# 12V-Rail_IGVC_14-15.net
KiCad netlist of a schematic drawn in EAGLE
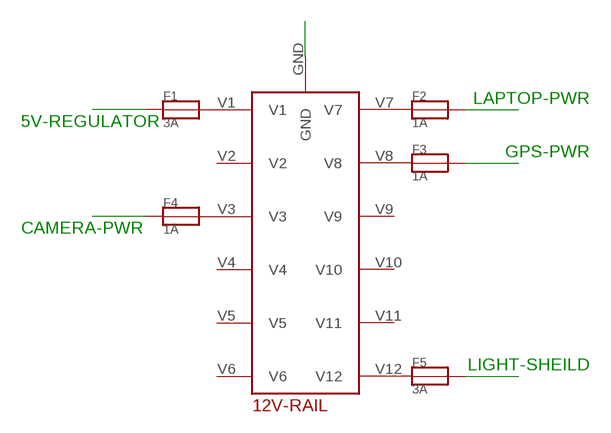
[diagram p0: schematic, sheet 1]

(export (version "E")
  (design (tool "Eeschema 10.0.6"))
  (components
    (comp (ref "12V-RAIL")
      (value "FUSEBLOCK-12")
      (footprint "eagle-import:FUSEBLOCK-12PT")
      (libsource (lib "eagle-import") (part "FUSEBLOCK-12"))
    )
    (comp (ref "F1")
      (value "3A")
      (footprint "eagle-import:FUSE")
      (libsource (lib "eagle-import") (part "FUSE"))
    )
    (comp (ref "F2")
      (value "1A")
      (footprint "eagle-import:FUSE")
      (libsource (lib "eagle-import") (part "FUSE"))
    )
    (comp (ref "F3")
      (value "1A")
      (footprint "eagle-import:FUSE")
      (libsource (lib "eagle-import") (part "FUSE"))
    )
    (comp (ref "F4")
      (value "1A")
      (footprint "eagle-import:FUSE")
      (libsource (lib "eagle-import") (part "FUSE"))
    )
    (comp (ref "F5")
      (value "3A")
      (footprint "eagle-import:FUSE")
      (libsource (lib "eagle-import") (part "FUSE"))
    )
  )
  (nets
    (net (code "1") (name "/V2") (class "Default")
      (node (ref "12V-RAIL") (pin "V2") (pinfunction "V2_V2") (pintype "power_in"))
    )
    (net (code "2") (name "/V4") (class "Default")
      (node (ref "12V-RAIL") (pin "V4") (pinfunction "V4_V4") (pintype "power_in"))
    )
    (net (code "3") (name "/V5") (class "Default")
      (node (ref "12V-RAIL") (pin "V5") (pinfunction "V5_V5") (pintype "power_in"))
    )
    (net (code "4") (name "/V6") (class "Default")
      (node (ref "12V-RAIL") (pin "V6") (pinfunction "V6_V6") (pintype "power_in"))
    )
    (net (code "5") (name "/V9") (class "Default")
      (node (ref "12V-RAIL") (pin "V9") (pinfunction "V9_V9") (pintype "power_in"))
    )
    (net (code "6") (name "/V10") (class "Default")
      (node (ref "12V-RAIL") (pin "V10") (pinfunction "V10_V10") (pintype "power_in"))
    )
    (net (code "7") (name "/V11") (class "Default")
      (node (ref "12V-RAIL") (pin "V11") (pinfunction "V11_V11") (pintype "power_in"))
    )
    (net (code "8") (name "Net-(12V-RAIL-PadV1)") (class "Default")
      (node (ref "12V-RAIL") (pin "V1") (pinfunction "V1_V1") (pintype "power_in"))
      (node (ref "F1") (pin "P$2") (pinfunction "P$2_P$2") (pintype "bidirectional"))
    )
    (net (code "9") (name "Net-(12V-RAIL-PadV3)") (class "Default")
      (node (ref "12V-RAIL") (pin "V3") (pinfunction "V3_V3") (pintype "power_in"))
      (node (ref "F4") (pin "P$2") (pinfunction "P$2_P$2") (pintype "bidirectional"))
    )
    (net (code "10") (name "Net-(12V-RAIL-PadV7)") (class "Default")
      (node (ref "12V-RAIL") (pin "V7") (pinfunction "V7_V7") (pintype "power_in"))
      (node (ref "F2") (pin "P$1") (pinfunction "P$1_P$1") (pintype "bidirectional"))
    )
    (net (code "11") (name "Net-(12V-RAIL-PadV8)") (class "Default")
      (node (ref "12V-RAIL") (pin "V8") (pinfunction "V8_V8") (pintype "power_in"))
      (node (ref "F3") (pin "P$1") (pinfunction "P$1_P$1") (pintype "bidirectional"))
    )
    (net (code "12") (name "Net-(12V-RAIL-PadV12)") (class "Default")
      (node (ref "12V-RAIL") (pin "V12") (pinfunction "V12_V12") (pintype "power_in"))
      (node (ref "F5") (pin "P$1") (pinfunction "P$1_P$1") (pintype "bidirectional"))
    )
    (net (code "13") (name "unconnected-(12V-RAIL-PadGND)") (class "Default")
      (node (ref "12V-RAIL") (pin "GND") (pinfunction "GND_GND") (pintype "power_in"))
    )
    (net (code "14") (name "unconnected-(F1-PadP$1)") (class "Default")
      (node (ref "F1") (pin "P$1") (pinfunction "P$1_P$1") (pintype "bidirectional"))
    )
    (net (code "15") (name "unconnected-(F2-PadP$2)") (class "Default")
      (node (ref "F2") (pin "P$2") (pinfunction "P$2_P$2") (pintype "bidirectional"))
    )
    (net (code "16") (name "unconnected-(F3-PadP$2)") (class "Default")
      (node (ref "F3") (pin "P$2") (pinfunction "P$2_P$2") (pintype "bidirectional"))
    )
    (net (code "17") (name "unconnected-(F4-PadP$1)") (class "Default")
      (node (ref "F4") (pin "P$1") (pinfunction "P$1_P$1") (pintype "bidirectional"))
    )
    (net (code "18") (name "unconnected-(F5-PadP$2)") (class "Default")
      (node (ref "F5") (pin "P$2") (pinfunction "P$2_P$2") (pintype "bidirectional"))
    )
  )
)
